# control_board.net
KiCad netlist of a schematic drawn in EAGLE
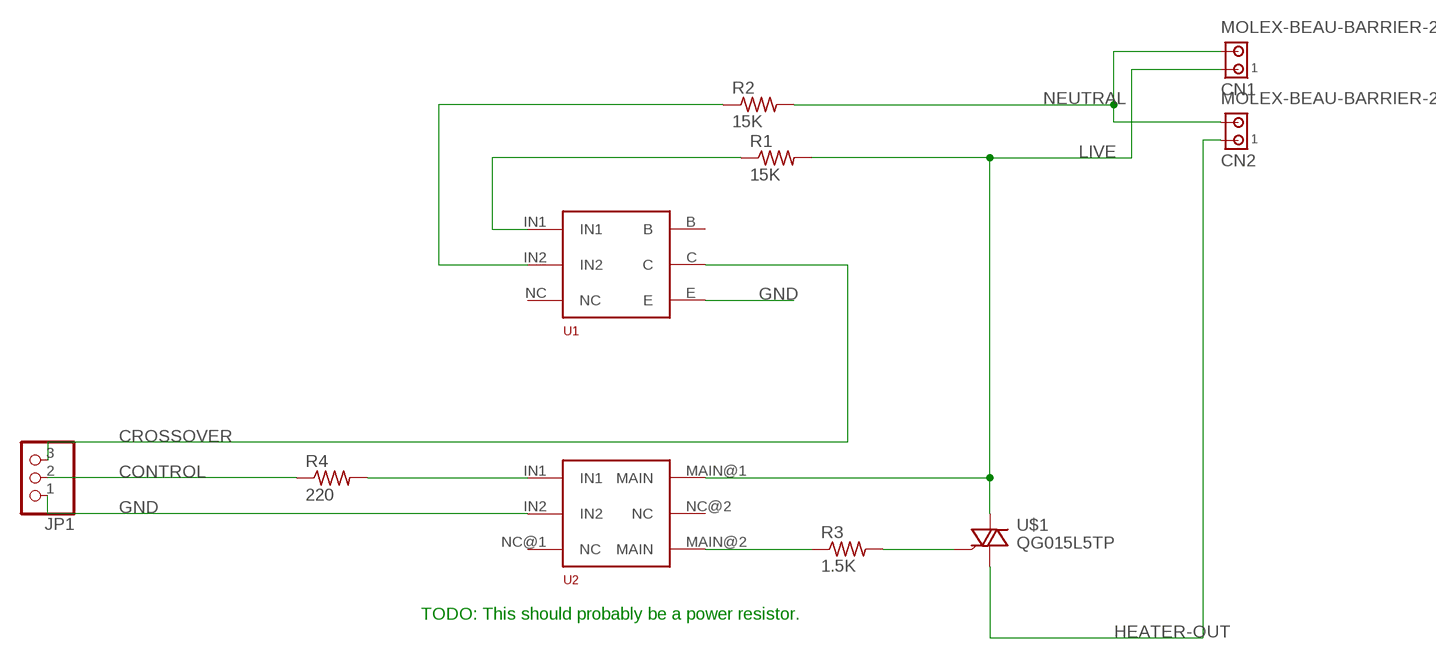
[diagram p0: schematic, sheet 1]

(export (version "E")
  (design (tool "Eeschema 10.0.6"))
  (components
    (comp (ref "CN1")
      (value "MOLEX-BEAU-BARRIER-2")
      (footprint "eagle-import:MOLEX-BEAU-BARRIER-2")
      (libsource (lib "eagle-import") (part "MOLEX-BEAU-BARRIER-2"))
    )
    (comp (ref "CN2")
      (value "MOLEX-BEAU-BARRIER-2")
      (footprint "eagle-import:MOLEX-BEAU-BARRIER-2")
      (libsource (lib "eagle-import") (part "MOLEX-BEAU-BARRIER-2"))
    )
    (comp (ref "JP1")
      (value "PINHD-1X3/90")
      (footprint "eagle-import:1X03_90")
      (libsource (lib "eagle-import") (part "PINHD-1X3/90"))
    )
    (comp (ref "R1")
      (value "15K")
      (footprint "eagle-import:RSF100")
      (libsource (lib "eagle-import") (part "RSF100JB-73"))
    )
    (comp (ref "R2")
      (value "15K")
      (footprint "eagle-import:RSF100")
      (libsource (lib "eagle-import") (part "RSF100JB-73"))
    )
    (comp (ref "R3")
      (value "1.5K")
      (footprint "eagle-import:CR-25")
      (libsource (lib "eagle-import") (part "YAGEO_CFR"))
    )
    (comp (ref "R4")
      (value "220")
      (footprint "eagle-import:CR-25")
      (libsource (lib "eagle-import") (part "YAGEO_CFR"))
    )
    (comp (ref "U$1")
      (value "QG015L5TP")
      (footprint "eagle-import:QG015L5TP")
      (libsource (lib "eagle-import") (part "QG015L5TP"))
    )
    (comp (ref "U1")
      (value "H11AA4M")
      (footprint "eagle-import:H11AA4M")
      (libsource (lib "eagle-import") (part "H11AA4M"))
    )
    (comp (ref "U2")
      (value "MOC3052M")
      (footprint "eagle-import:MOC3052M")
      (libsource (lib "eagle-import") (part "MOC3052M"))
    )
  )
  (nets
    (net (code "1") (name "/CONTROL") (class "Default")
      (node (ref "JP1") (pin "2") (pinfunction "2_2") (pintype "passive"))
      (node (ref "R4") (pin "P$1") (pinfunction "1_P$1") (pintype "passive"))
    )
    (net (code "2") (name "/CROSSOVER") (class "Default")
      (node (ref "JP1") (pin "3") (pinfunction "3_3") (pintype "passive"))
      (node (ref "U1") (pin "C") (pinfunction "C_C") (pintype "bidirectional"))
    )
    (net (code "3") (name "/GND") (class "Default")
      (node (ref "JP1") (pin "1") (pinfunction "1_1") (pintype "passive"))
      (node (ref "U1") (pin "E") (pinfunction "E_E") (pintype "bidirectional"))
      (node (ref "U2") (pin "IN2") (pinfunction "IN2_IN2") (pintype "passive"))
    )
    (net (code "4") (name "/HEATER-OUT") (class "Default")
      (node (ref "CN2") (pin "P1") (pinfunction "1_P1") (pintype "passive"))
      (node (ref "U$1") (pin "P$3") (pinfunction "A1_P$3") (pintype "passive"))
    )
    (net (code "5") (name "/LIVE") (class "Default")
      (node (ref "CN1") (pin "P1") (pinfunction "1_P1") (pintype "passive"))
      (node (ref "R1") (pin "P$2") (pinfunction "2_P$2") (pintype "passive"))
      (node (ref "U$1") (pin "P$2") (pinfunction "A2_P$2") (pintype "passive"))
      (node (ref "U2") (pin "MAIN@1") (pinfunction "MAIN_MAIN@1") (pintype "bidirectional"))
    )
    (net (code "6") (name "/NEUTRAL") (class "Default")
      (node (ref "CN1") (pin "P2") (pinfunction "2_P2") (pintype "passive"))
      (node (ref "CN2") (pin "P2") (pinfunction "2_P2") (pintype "passive"))
      (node (ref "R2") (pin "P$2") (pinfunction "2_P$2") (pintype "passive"))
    )
    (net (code "7") (name "Net-(R1-1)") (class "Default")
      (node (ref "R1") (pin "P$1") (pinfunction "1_P$1") (pintype "passive"))
      (node (ref "U1") (pin "IN1") (pinfunction "IN1_IN1") (pintype "passive"))
    )
    (net (code "8") (name "Net-(R2-1)") (class "Default")
      (node (ref "R2") (pin "P$1") (pinfunction "1_P$1") (pintype "passive"))
      (node (ref "U1") (pin "IN2") (pinfunction "IN2_IN2") (pintype "passive"))
    )
    (net (code "9") (name "Net-(R3-1)") (class "Default")
      (node (ref "R3") (pin "P$1") (pinfunction "1_P$1") (pintype "passive"))
      (node (ref "U2") (pin "MAIN@2") (pinfunction "MAIN_MAIN@2") (pintype "bidirectional"))
    )
    (net (code "10") (name "Net-(R3-2)") (class "Default")
      (node (ref "R3") (pin "P$2") (pinfunction "2_P$2") (pintype "passive"))
      (node (ref "U$1") (pin "P$1") (pinfunction "G_P$1") (pintype "passive"))
    )
    (net (code "11") (name "Net-(R4-2)") (class "Default")
      (node (ref "R4") (pin "P$2") (pinfunction "2_P$2") (pintype "passive"))
      (node (ref "U2") (pin "IN1") (pinfunction "IN1_IN1") (pintype "passive"))
    )
    (net (code "12") (name "unconnected-(U1-PadB)") (class "Default")
      (node (ref "U1") (pin "B") (pinfunction "B_B") (pintype "bidirectional"))
    )
    (net (code "13") (name "unconnected-(U1-PadNC)") (class "Default")
      (node (ref "U1") (pin "NC") (pinfunction "NC_NC") (pintype "no_connect"))
    )
    (net (code "14") (name "unconnected-(U2-NC-PadNC@1)") (class "Default")
      (node (ref "U2") (pin "NC@1") (pinfunction "NC_NC@1") (pintype "no_connect"))
    )
    (net (code "15") (name "unconnected-(U2-NC-PadNC@2)") (class "Default")
      (node (ref "U2") (pin "NC@2") (pinfunction "NC_NC@2") (pintype "no_connect"))
    )
  )
)
